# ah.net
KiCad netlist of a schematic drawn in EAGLE
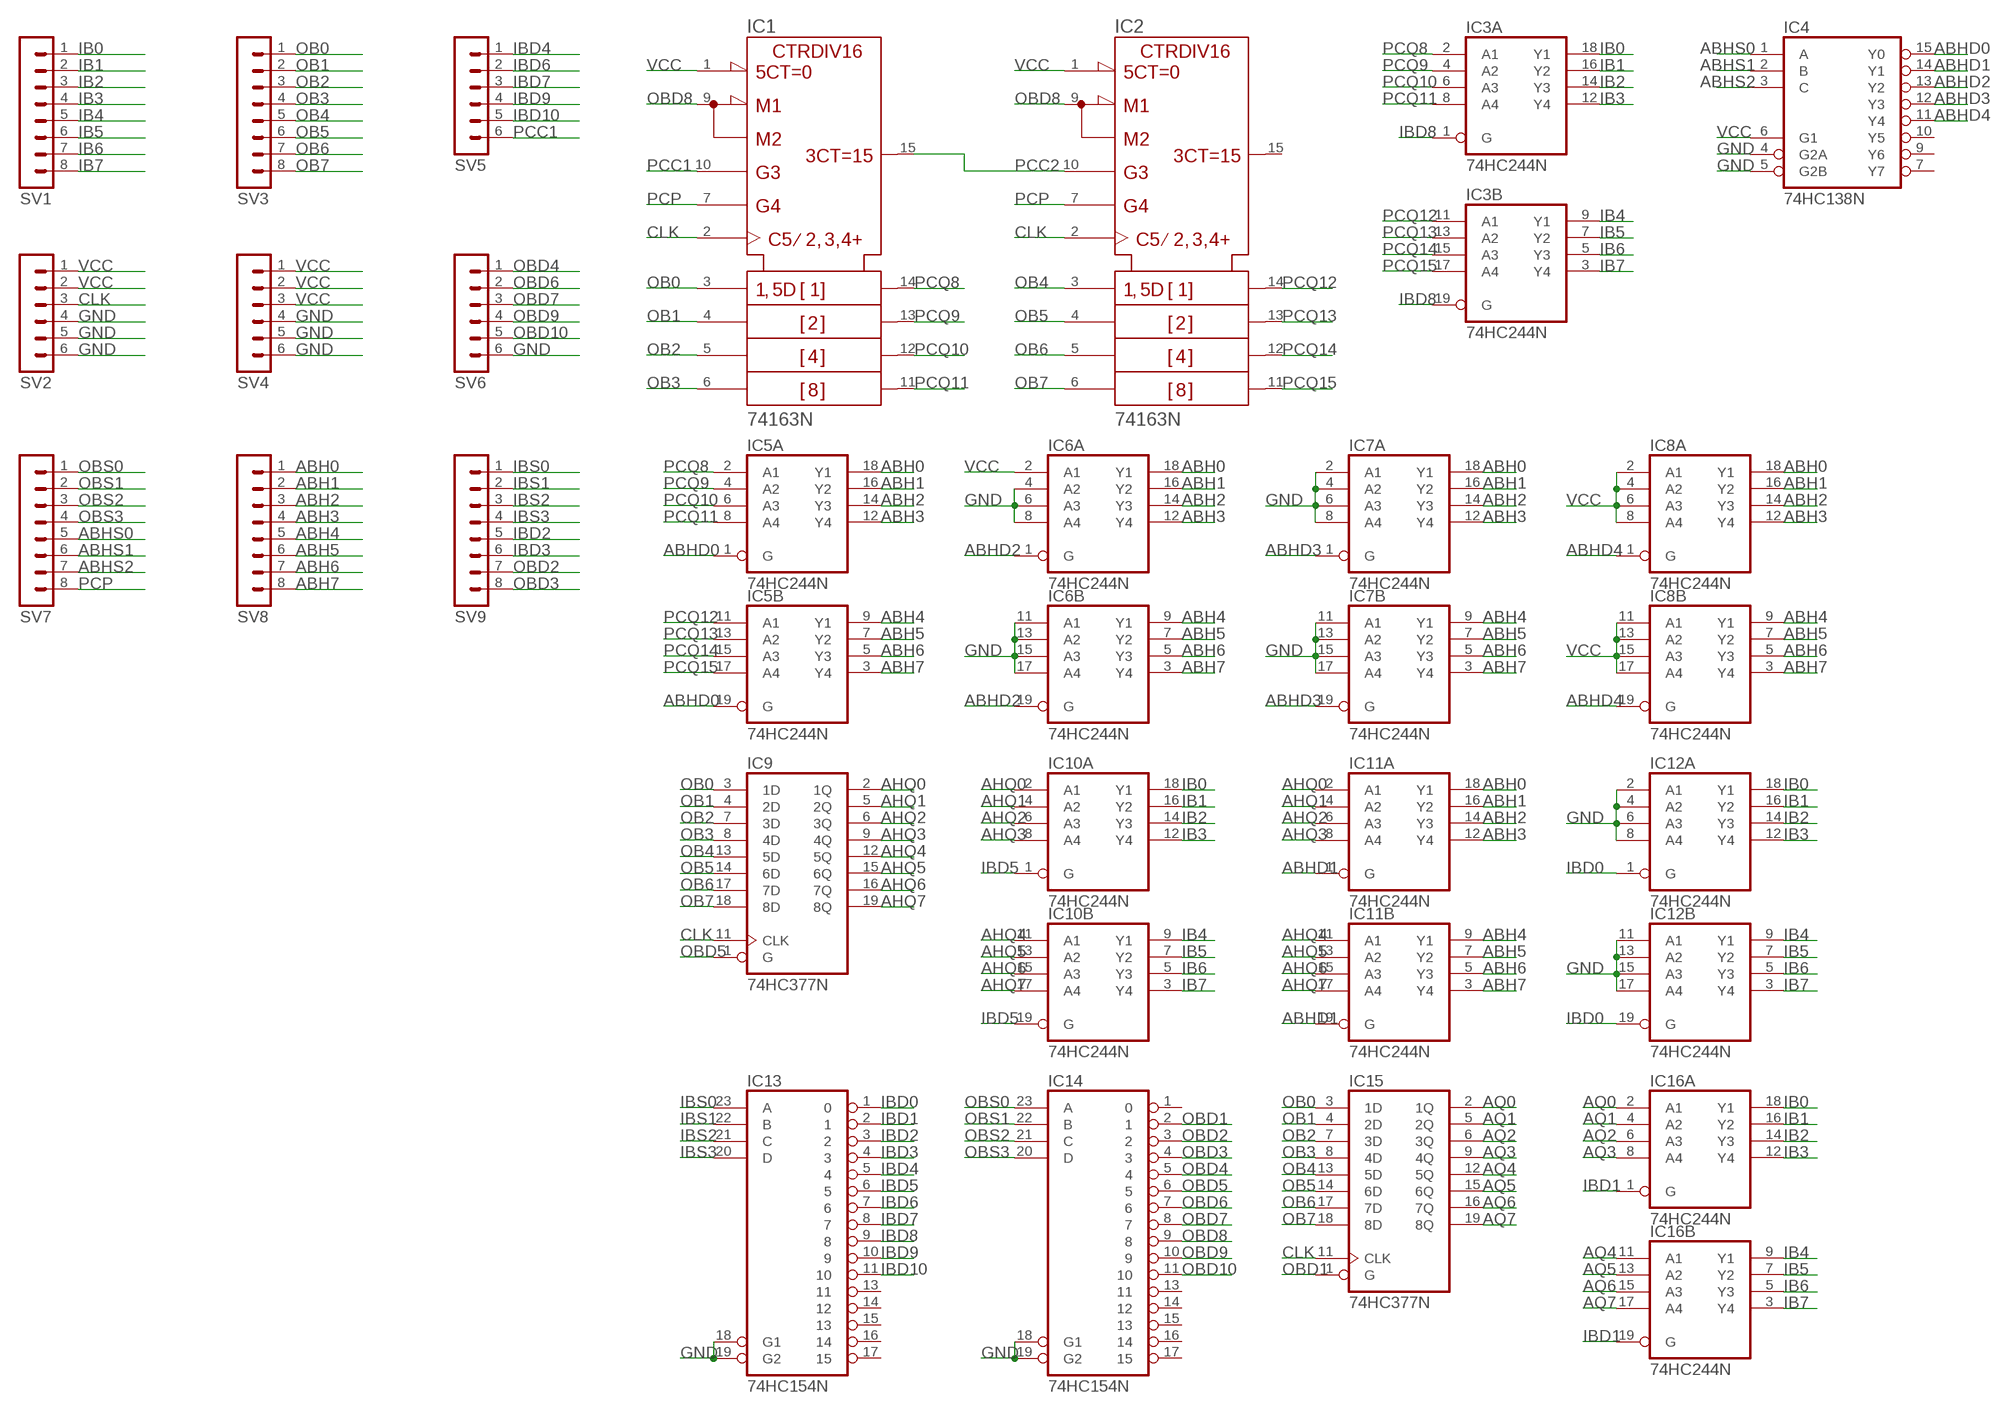
[diagram p0: schematic, sheet 1]

(export (version "E")
  (design (tool "Eeschema 10.0.6"))
  (components
    (comp (ref "IC1")
      (value "74163N")
      (footprint "eagle-import:DIL16")
      (libsource (lib "eagle-import") (part "74163N"))
    )
    (comp (ref "IC2")
      (value "74163N")
      (footprint "eagle-import:DIL16")
      (libsource (lib "eagle-import") (part "74163N"))
    )
    (comp (ref "IC3")
      (value "74HC244N")
      (footprint "eagle-import:DIL20")
      (libsource (lib "eagle-import") (part "74244NHC"))
    )
    (comp (ref "IC4")
      (value "74HC138N")
      (footprint "eagle-import:DIL16")
      (libsource (lib "eagle-import") (part "74138NHC"))
    )
    (comp (ref "IC5")
      (value "74HC244N")
      (footprint "eagle-import:DIL20")
      (libsource (lib "eagle-import") (part "74244NHC"))
    )
    (comp (ref "IC6")
      (value "74HC244N")
      (footprint "eagle-import:DIL20")
      (libsource (lib "eagle-import") (part "74244NHC"))
    )
    (comp (ref "IC7")
      (value "74HC244N")
      (footprint "eagle-import:DIL20")
      (libsource (lib "eagle-import") (part "74244NHC"))
    )
    (comp (ref "IC8")
      (value "74HC244N")
      (footprint "eagle-import:DIL20")
      (libsource (lib "eagle-import") (part "74244NHC"))
    )
    (comp (ref "IC9")
      (value "74HC377N")
      (footprint "eagle-import:DIL20")
      (libsource (lib "eagle-import") (part "74377NHC"))
    )
    (comp (ref "IC10")
      (value "74HC244N")
      (footprint "eagle-import:DIL20")
      (libsource (lib "eagle-import") (part "74244NHC"))
    )
    (comp (ref "IC11")
      (value "74HC244N")
      (footprint "eagle-import:DIL20")
      (libsource (lib "eagle-import") (part "74244NHC"))
    )
    (comp (ref "IC12")
      (value "74HC244N")
      (footprint "eagle-import:DIL20")
      (libsource (lib "eagle-import") (part "74244NHC"))
    )
    (comp (ref "IC13")
      (value "74HC154N")
      (footprint "eagle-import:DIL24-6")
      (libsource (lib "eagle-import") (part "74154NHC"))
    )
    (comp (ref "IC14")
      (value "74HC154N")
      (footprint "eagle-import:DIL24-6")
      (libsource (lib "eagle-import") (part "74154NHC"))
    )
    (comp (ref "IC15")
      (value "74HC377N")
      (footprint "eagle-import:DIL20")
      (libsource (lib "eagle-import") (part "74377NHC"))
    )
    (comp (ref "IC16")
      (value "74HC244N")
      (footprint "eagle-import:DIL20")
      (libsource (lib "eagle-import") (part "74244NHC"))
    )
    (comp (ref "SV1")
      (value "MA08-1")
      (footprint "eagle-import:MA08-1")
      (libsource (lib "eagle-import") (part "MA08-1"))
    )
    (comp (ref "SV2")
      (value "MA06-1")
      (footprint "eagle-import:MA06-1")
      (libsource (lib "eagle-import") (part "MA06-1"))
    )
    (comp (ref "SV3")
      (value "MA08-1")
      (footprint "eagle-import:MA08-1")
      (libsource (lib "eagle-import") (part "MA08-1"))
    )
    (comp (ref "SV4")
      (value "MA06-1")
      (footprint "eagle-import:MA06-1")
      (libsource (lib "eagle-import") (part "MA06-1"))
    )
    (comp (ref "SV5")
      (value "MA06-1")
      (footprint "eagle-import:MA06-1")
      (libsource (lib "eagle-import") (part "MA06-1"))
    )
    (comp (ref "SV6")
      (value "MA06-1")
      (footprint "eagle-import:MA06-1")
      (libsource (lib "eagle-import") (part "MA06-1"))
    )
    (comp (ref "SV7")
      (value "MA08-1")
      (footprint "eagle-import:MA08-1")
      (libsource (lib "eagle-import") (part "MA08-1"))
    )
    (comp (ref "SV8")
      (value "MA08-1")
      (footprint "eagle-import:MA08-1")
      (libsource (lib "eagle-import") (part "MA08-1"))
    )
    (comp (ref "SV9")
      (value "MA08-1")
      (footprint "eagle-import:MA08-1")
      (libsource (lib "eagle-import") (part "MA08-1"))
    )
  )
  (nets
    (net (code "1") (name "/ABH0") (class "Default")
      (node (ref "IC11") (pin "18") (pinfunction "Y1_18") (pintype "tri_state"))
      (node (ref "IC5") (pin "18") (pinfunction "Y1_18") (pintype "tri_state"))
      (node (ref "IC6") (pin "18") (pinfunction "Y1_18") (pintype "tri_state"))
      (node (ref "IC7") (pin "18") (pinfunction "Y1_18") (pintype "tri_state"))
      (node (ref "IC8") (pin "18") (pinfunction "Y1_18") (pintype "tri_state"))
      (node (ref "SV8") (pin "1") (pinfunction "1_1") (pintype "passive"))
    )
    (net (code "2") (name "/ABH1") (class "Default")
      (node (ref "IC11") (pin "16") (pinfunction "Y2_16") (pintype "tri_state"))
      (node (ref "IC5") (pin "16") (pinfunction "Y2_16") (pintype "tri_state"))
      (node (ref "IC6") (pin "16") (pinfunction "Y2_16") (pintype "tri_state"))
      (node (ref "IC7") (pin "16") (pinfunction "Y2_16") (pintype "tri_state"))
      (node (ref "IC8") (pin "16") (pinfunction "Y2_16") (pintype "tri_state"))
      (node (ref "SV8") (pin "2") (pinfunction "2_2") (pintype "passive"))
    )
    (net (code "3") (name "/ABH2") (class "Default")
      (node (ref "IC11") (pin "14") (pinfunction "Y3_14") (pintype "tri_state"))
      (node (ref "IC5") (pin "14") (pinfunction "Y3_14") (pintype "tri_state"))
      (node (ref "IC6") (pin "14") (pinfunction "Y3_14") (pintype "tri_state"))
      (node (ref "IC7") (pin "14") (pinfunction "Y3_14") (pintype "tri_state"))
      (node (ref "IC8") (pin "14") (pinfunction "Y3_14") (pintype "tri_state"))
      (node (ref "SV8") (pin "3") (pinfunction "3_3") (pintype "passive"))
    )
    (net (code "4") (name "/ABH3") (class "Default")
      (node (ref "IC11") (pin "12") (pinfunction "Y4_12") (pintype "tri_state"))
      (node (ref "IC5") (pin "12") (pinfunction "Y4_12") (pintype "tri_state"))
      (node (ref "IC6") (pin "12") (pinfunction "Y4_12") (pintype "tri_state"))
      (node (ref "IC7") (pin "12") (pinfunction "Y4_12") (pintype "tri_state"))
      (node (ref "IC8") (pin "12") (pinfunction "Y4_12") (pintype "tri_state"))
      (node (ref "SV8") (pin "4") (pinfunction "4_4") (pintype "passive"))
    )
    (net (code "5") (name "/ABH4") (class "Default")
      (node (ref "IC11") (pin "9") (pinfunction "Y1_9") (pintype "tri_state"))
      (node (ref "IC5") (pin "9") (pinfunction "Y1_9") (pintype "tri_state"))
      (node (ref "IC6") (pin "9") (pinfunction "Y1_9") (pintype "tri_state"))
      (node (ref "IC7") (pin "9") (pinfunction "Y1_9") (pintype "tri_state"))
      (node (ref "IC8") (pin "9") (pinfunction "Y1_9") (pintype "tri_state"))
      (node (ref "SV8") (pin "5") (pinfunction "5_5") (pintype "passive"))
    )
    (net (code "6") (name "/ABH5") (class "Default")
      (node (ref "IC11") (pin "7") (pinfunction "Y2_7") (pintype "tri_state"))
      (node (ref "IC5") (pin "7") (pinfunction "Y2_7") (pintype "tri_state"))
      (node (ref "IC6") (pin "7") (pinfunction "Y2_7") (pintype "tri_state"))
      (node (ref "IC7") (pin "7") (pinfunction "Y2_7") (pintype "tri_state"))
      (node (ref "IC8") (pin "7") (pinfunction "Y2_7") (pintype "tri_state"))
      (node (ref "SV8") (pin "6") (pinfunction "6_6") (pintype "passive"))
    )
    (net (code "7") (name "/ABH6") (class "Default")
      (node (ref "IC11") (pin "5") (pinfunction "Y3_5") (pintype "tri_state"))
      (node (ref "IC5") (pin "5") (pinfunction "Y3_5") (pintype "tri_state"))
      (node (ref "IC6") (pin "5") (pinfunction "Y3_5") (pintype "tri_state"))
      (node (ref "IC7") (pin "5") (pinfunction "Y3_5") (pintype "tri_state"))
      (node (ref "IC8") (pin "5") (pinfunction "Y3_5") (pintype "tri_state"))
      (node (ref "SV8") (pin "7") (pinfunction "7_7") (pintype "passive"))
    )
    (net (code "8") (name "/ABH7") (class "Default")
      (node (ref "IC11") (pin "3") (pinfunction "Y4_3") (pintype "tri_state"))
      (node (ref "IC5") (pin "3") (pinfunction "Y4_3") (pintype "tri_state"))
      (node (ref "IC6") (pin "3") (pinfunction "Y4_3") (pintype "tri_state"))
      (node (ref "IC7") (pin "3") (pinfunction "Y4_3") (pintype "tri_state"))
      (node (ref "IC8") (pin "3") (pinfunction "Y4_3") (pintype "tri_state"))
      (node (ref "SV8") (pin "8") (pinfunction "8_8") (pintype "passive"))
    )
    (net (code "9") (name "/ABHD0") (class "Default")
      (node (ref "IC4") (pin "15") (pinfunction "Y0_15") (pintype "output"))
      (node (ref "IC5") (pin "1") (pinfunction "G_1") (pintype "input"))
      (node (ref "IC5") (pin "19") (pinfunction "G_19") (pintype "input"))
    )
    (net (code "10") (name "/ABHD1") (class "Default")
      (node (ref "IC11") (pin "1") (pinfunction "G_1") (pintype "input"))
      (node (ref "IC11") (pin "19") (pinfunction "G_19") (pintype "input"))
      (node (ref "IC4") (pin "14") (pinfunction "Y1_14") (pintype "output"))
    )
    (net (code "11") (name "/ABHD2") (class "Default")
      (node (ref "IC4") (pin "13") (pinfunction "Y2_13") (pintype "output"))
      (node (ref "IC6") (pin "1") (pinfunction "G_1") (pintype "input"))
      (node (ref "IC6") (pin "19") (pinfunction "G_19") (pintype "input"))
    )
    (net (code "12") (name "/ABHD3") (class "Default")
      (node (ref "IC4") (pin "12") (pinfunction "Y3_12") (pintype "output"))
      (node (ref "IC7") (pin "1") (pinfunction "G_1") (pintype "input"))
      (node (ref "IC7") (pin "19") (pinfunction "G_19") (pintype "input"))
    )
    (net (code "13") (name "/ABHD4") (class "Default")
      (node (ref "IC4") (pin "11") (pinfunction "Y4_11") (pintype "output"))
      (node (ref "IC8") (pin "1") (pinfunction "G_1") (pintype "input"))
      (node (ref "IC8") (pin "19") (pinfunction "G_19") (pintype "input"))
    )
    (net (code "14") (name "/ABHS0") (class "Default")
      (node (ref "IC4") (pin "1") (pinfunction "A_1") (pintype "input"))
      (node (ref "SV7") (pin "5") (pinfunction "5_5") (pintype "passive"))
    )
    (net (code "15") (name "/ABHS1") (class "Default")
      (node (ref "IC4") (pin "2") (pinfunction "B_2") (pintype "input"))
      (node (ref "SV7") (pin "6") (pinfunction "6_6") (pintype "passive"))
    )
    (net (code "16") (name "/ABHS2") (class "Default")
      (node (ref "IC4") (pin "3") (pinfunction "C_3") (pintype "input"))
      (node (ref "SV7") (pin "7") (pinfunction "7_7") (pintype "passive"))
    )
    (net (code "17") (name "/AHQ0") (class "Default")
      (node (ref "IC10") (pin "2") (pinfunction "A1_2") (pintype "input"))
      (node (ref "IC11") (pin "2") (pinfunction "A1_2") (pintype "input"))
      (node (ref "IC9") (pin "2") (pinfunction "1Q_2") (pintype "output"))
    )
    (net (code "18") (name "/AHQ1") (class "Default")
      (node (ref "IC10") (pin "4") (pinfunction "A2_4") (pintype "input"))
      (node (ref "IC11") (pin "4") (pinfunction "A2_4") (pintype "input"))
      (node (ref "IC9") (pin "5") (pinfunction "2Q_5") (pintype "output"))
    )
    (net (code "19") (name "/AHQ2") (class "Default")
      (node (ref "IC10") (pin "6") (pinfunction "A3_6") (pintype "input"))
      (node (ref "IC11") (pin "6") (pinfunction "A3_6") (pintype "input"))
      (node (ref "IC9") (pin "6") (pinfunction "3Q_6") (pintype "output"))
    )
    (net (code "20") (name "/AHQ3") (class "Default")
      (node (ref "IC10") (pin "8") (pinfunction "A4_8") (pintype "input"))
      (node (ref "IC11") (pin "8") (pinfunction "A4_8") (pintype "input"))
      (node (ref "IC9") (pin "9") (pinfunction "4Q_9") (pintype "output"))
    )
    (net (code "21") (name "/AHQ4") (class "Default")
      (node (ref "IC10") (pin "11") (pinfunction "A1_11") (pintype "input"))
      (node (ref "IC11") (pin "11") (pinfunction "A1_11") (pintype "input"))
      (node (ref "IC9") (pin "12") (pinfunction "5Q_12") (pintype "output"))
    )
    (net (code "22") (name "/AHQ5") (class "Default")
      (node (ref "IC10") (pin "13") (pinfunction "A2_13") (pintype "input"))
      (node (ref "IC11") (pin "13") (pinfunction "A2_13") (pintype "input"))
      (node (ref "IC9") (pin "15") (pinfunction "6Q_15") (pintype "output"))
    )
    (net (code "23") (name "/AHQ6") (class "Default")
      (node (ref "IC10") (pin "15") (pinfunction "A3_15") (pintype "input"))
      (node (ref "IC11") (pin "15") (pinfunction "A3_15") (pintype "input"))
      (node (ref "IC9") (pin "16") (pinfunction "7Q_16") (pintype "output"))
    )
    (net (code "24") (name "/AHQ7") (class "Default")
      (node (ref "IC10") (pin "17") (pinfunction "A4_17") (pintype "input"))
      (node (ref "IC11") (pin "17") (pinfunction "A4_17") (pintype "input"))
      (node (ref "IC9") (pin "19") (pinfunction "8Q_19") (pintype "output"))
    )
    (net (code "25") (name "/AQ0") (class "Default")
      (node (ref "IC15") (pin "2") (pinfunction "1Q_2") (pintype "output"))
      (node (ref "IC16") (pin "2") (pinfunction "A1_2") (pintype "input"))
    )
    (net (code "26") (name "/AQ1") (class "Default")
      (node (ref "IC15") (pin "5") (pinfunction "2Q_5") (pintype "output"))
      (node (ref "IC16") (pin "4") (pinfunction "A2_4") (pintype "input"))
    )
    (net (code "27") (name "/AQ2") (class "Default")
      (node (ref "IC15") (pin "6") (pinfunction "3Q_6") (pintype "output"))
      (node (ref "IC16") (pin "6") (pinfunction "A3_6") (pintype "input"))
    )
    (net (code "28") (name "/AQ3") (class "Default")
      (node (ref "IC15") (pin "9") (pinfunction "4Q_9") (pintype "output"))
      (node (ref "IC16") (pin "8") (pinfunction "A4_8") (pintype "input"))
    )
    (net (code "29") (name "/AQ4") (class "Default")
      (node (ref "IC15") (pin "12") (pinfunction "5Q_12") (pintype "output"))
      (node (ref "IC16") (pin "11") (pinfunction "A1_11") (pintype "input"))
    )
    (net (code "30") (name "/AQ5") (class "Default")
      (node (ref "IC15") (pin "15") (pinfunction "6Q_15") (pintype "output"))
      (node (ref "IC16") (pin "13") (pinfunction "A2_13") (pintype "input"))
    )
    (net (code "31") (name "/AQ6") (class "Default")
      (node (ref "IC15") (pin "16") (pinfunction "7Q_16") (pintype "output"))
      (node (ref "IC16") (pin "15") (pinfunction "A3_15") (pintype "input"))
    )
    (net (code "32") (name "/AQ7") (class "Default")
      (node (ref "IC15") (pin "19") (pinfunction "8Q_19") (pintype "output"))
      (node (ref "IC16") (pin "17") (pinfunction "A4_17") (pintype "input"))
    )
    (net (code "33") (name "/CLK") (class "Default")
      (node (ref "IC1") (pin "2") (pinfunction "CLK_2") (pintype "input"))
      (node (ref "IC15") (pin "11") (pinfunction "CLK_11") (pintype "input"))
      (node (ref "IC2") (pin "2") (pinfunction "CLK_2") (pintype "input"))
      (node (ref "IC9") (pin "11") (pinfunction "CLK_11") (pintype "input"))
      (node (ref "SV2") (pin "3") (pinfunction "3_3") (pintype "passive"))
    )
    (net (code "34") (name "/GND") (class "Default")
      (node (ref "IC12") (pin "11") (pinfunction "A1_11") (pintype "input"))
      (node (ref "IC12") (pin "13") (pinfunction "A2_13") (pintype "input"))
      (node (ref "IC12") (pin "15") (pinfunction "A3_15") (pintype "input"))
      (node (ref "IC12") (pin "17") (pinfunction "A4_17") (pintype "input"))
      (node (ref "IC12") (pin "2") (pinfunction "A1_2") (pintype "input"))
      (node (ref "IC12") (pin "4") (pinfunction "A2_4") (pintype "input"))
      (node (ref "IC12") (pin "6") (pinfunction "A3_6") (pintype "input"))
      (node (ref "IC12") (pin "8") (pinfunction "A4_8") (pintype "input"))
      (node (ref "IC13") (pin "18") (pinfunction "G1_18") (pintype "input"))
      (node (ref "IC13") (pin "19") (pinfunction "G2_19") (pintype "input"))
      (node (ref "IC14") (pin "18") (pinfunction "G1_18") (pintype "input"))
      (node (ref "IC14") (pin "19") (pinfunction "G2_19") (pintype "input"))
      (node (ref "IC4") (pin "4") (pinfunction "G2A_4") (pintype "input"))
      (node (ref "IC4") (pin "5") (pinfunction "G2B_5") (pintype "input"))
      (node (ref "IC6") (pin "11") (pinfunction "A1_11") (pintype "input"))
      (node (ref "IC6") (pin "13") (pinfunction "A2_13") (pintype "input"))
      (node (ref "IC6") (pin "15") (pinfunction "A3_15") (pintype "input"))
      (node (ref "IC6") (pin "17") (pinfunction "A4_17") (pintype "input"))
      (node (ref "IC6") (pin "4") (pinfunction "A2_4") (pintype "input"))
      (node (ref "IC6") (pin "6") (pinfunction "A3_6") (pintype "input"))
      (node (ref "IC6") (pin "8") (pinfunction "A4_8") (pintype "input"))
      (node (ref "IC7") (pin "11") (pinfunction "A1_11") (pintype "input"))
      (node (ref "IC7") (pin "13") (pinfunction "A2_13") (pintype "input"))
      (node (ref "IC7") (pin "15") (pinfunction "A3_15") (pintype "input"))
      (node (ref "IC7") (pin "17") (pinfunction "A4_17") (pintype "input"))
      (node (ref "IC7") (pin "2") (pinfunction "A1_2") (pintype "input"))
      (node (ref "IC7") (pin "4") (pinfunction "A2_4") (pintype "input"))
      (node (ref "IC7") (pin "6") (pinfunction "A3_6") (pintype "input"))
      (node (ref "IC7") (pin "8") (pinfunction "A4_8") (pintype "input"))
      (node (ref "SV2") (pin "4") (pinfunction "4_4") (pintype "passive"))
      (node (ref "SV2") (pin "5") (pinfunction "5_5") (pintype "passive"))
      (node (ref "SV2") (pin "6") (pinfunction "6_6") (pintype "passive"))
      (node (ref "SV4") (pin "4") (pinfunction "4_4") (pintype "passive"))
      (node (ref "SV4") (pin "5") (pinfunction "5_5") (pintype "passive"))
      (node (ref "SV4") (pin "6") (pinfunction "6_6") (pintype "passive"))
      (node (ref "SV6") (pin "6") (pinfunction "6_6") (pintype "passive"))
    )
    (net (code "35") (name "/IB0") (class "Default")
      (node (ref "IC10") (pin "18") (pinfunction "Y1_18") (pintype "tri_state"))
      (node (ref "IC12") (pin "18") (pinfunction "Y1_18") (pintype "tri_state"))
      (node (ref "IC16") (pin "18") (pinfunction "Y1_18") (pintype "tri_state"))
      (node (ref "IC3") (pin "18") (pinfunction "Y1_18") (pintype "tri_state"))
      (node (ref "SV1") (pin "1") (pinfunction "1_1") (pintype "passive"))
    )
    (net (code "36") (name "/IB1") (class "Default")
      (node (ref "IC10") (pin "16") (pinfunction "Y2_16") (pintype "tri_state"))
      (node (ref "IC12") (pin "16") (pinfunction "Y2_16") (pintype "tri_state"))
      (node (ref "IC16") (pin "16") (pinfunction "Y2_16") (pintype "tri_state"))
      (node (ref "IC3") (pin "16") (pinfunction "Y2_16") (pintype "tri_state"))
      (node (ref "SV1") (pin "2") (pinfunction "2_2") (pintype "passive"))
    )
    (net (code "37") (name "/IB2") (class "Default")
      (node (ref "IC10") (pin "14") (pinfunction "Y3_14") (pintype "tri_state"))
      (node (ref "IC12") (pin "14") (pinfunction "Y3_14") (pintype "tri_state"))
      (node (ref "IC16") (pin "14") (pinfunction "Y3_14") (pintype "tri_state"))
      (node (ref "IC3") (pin "14") (pinfunction "Y3_14") (pintype "tri_state"))
      (node (ref "SV1") (pin "3") (pinfunction "3_3") (pintype "passive"))
    )
    (net (code "38") (name "/IB3") (class "Default")
      (node (ref "IC10") (pin "12") (pinfunction "Y4_12") (pintype "tri_state"))
      (node (ref "IC12") (pin "12") (pinfunction "Y4_12") (pintype "tri_state"))
      (node (ref "IC16") (pin "12") (pinfunction "Y4_12") (pintype "tri_state"))
      (node (ref "IC3") (pin "12") (pinfunction "Y4_12") (pintype "tri_state"))
      (node (ref "SV1") (pin "4") (pinfunction "4_4") (pintype "passive"))
    )
    (net (code "39") (name "/IB4") (class "Default")
      (node (ref "IC10") (pin "9") (pinfunction "Y1_9") (pintype "tri_state"))
      (node (ref "IC12") (pin "9") (pinfunction "Y1_9") (pintype "tri_state"))
      (node (ref "IC16") (pin "9") (pinfunction "Y1_9") (pintype "tri_state"))
      (node (ref "IC3") (pin "9") (pinfunction "Y1_9") (pintype "tri_state"))
      (node (ref "SV1") (pin "5") (pinfunction "5_5") (pintype "passive"))
    )
    (net (code "40") (name "/IB5") (class "Default")
      (node (ref "IC10") (pin "7") (pinfunction "Y2_7") (pintype "tri_state"))
      (node (ref "IC12") (pin "7") (pinfunction "Y2_7") (pintype "tri_state"))
      (node (ref "IC16") (pin "7") (pinfunction "Y2_7") (pintype "tri_state"))
      (node (ref "IC3") (pin "7") (pinfunction "Y2_7") (pintype "tri_state"))
      (node (ref "SV1") (pin "6") (pinfunction "6_6") (pintype "passive"))
    )
    (net (code "41") (name "/IB6") (class "Default")
      (node (ref "IC10") (pin "5") (pinfunction "Y3_5") (pintype "tri_state"))
      (node (ref "IC12") (pin "5") (pinfunction "Y3_5") (pintype "tri_state"))
      (node (ref "IC16") (pin "5") (pinfunction "Y3_5") (pintype "tri_state"))
      (node (ref "IC3") (pin "5") (pinfunction "Y3_5") (pintype "tri_state"))
      (node (ref "SV1") (pin "7") (pinfunction "7_7") (pintype "passive"))
    )
    (net (code "42") (name "/IB7") (class "Default")
      (node (ref "IC10") (pin "3") (pinfunction "Y4_3") (pintype "tri_state"))
      (node (ref "IC12") (pin "3") (pinfunction "Y4_3") (pintype "tri_state"))
      (node (ref "IC16") (pin "3") (pinfunction "Y4_3") (pintype "tri_state"))
      (node (ref "IC3") (pin "3") (pinfunction "Y4_3") (pintype "tri_state"))
      (node (ref "SV1") (pin "8") (pinfunction "8_8") (pintype "passive"))
    )
    (net (code "43") (name "/IBD0") (class "Default")
      (node (ref "IC12") (pin "1") (pinfunction "G_1") (pintype "input"))
      (node (ref "IC12") (pin "19") (pinfunction "G_19") (pintype "input"))
      (node (ref "IC13") (pin "1") (pinfunction "0_1") (pintype "output"))
    )
    (net (code "44") (name "/IBD1") (class "Default")
      (node (ref "IC13") (pin "2") (pinfunction "1_2") (pintype "output"))
      (node (ref "IC16") (pin "1") (pinfunction "G_1") (pintype "input"))
      (node (ref "IC16") (pin "19") (pinfunction "G_19") (pintype "input"))
    )
    (net (code "45") (name "/IBD2") (class "Default")
      (node (ref "IC13") (pin "3") (pinfunction "2_3") (pintype "output"))
      (node (ref "SV9") (pin "5") (pinfunction "5_5") (pintype "passive"))
    )
    (net (code "46") (name "/IBD3") (class "Default")
      (node (ref "IC13") (pin "4") (pinfunction "3_4") (pintype "output"))
      (node (ref "SV9") (pin "6") (pinfunction "6_6") (pintype "passive"))
    )
    (net (code "47") (name "/IBD4") (class "Default")
      (node (ref "IC13") (pin "5") (pinfunction "4_5") (pintype "output"))
      (node (ref "SV5") (pin "1") (pinfunction "1_1") (pintype "passive"))
    )
    (net (code "48") (name "/IBD5") (class "Default")
      (node (ref "IC10") (pin "1") (pinfunction "G_1") (pintype "input"))
      (node (ref "IC10") (pin "19") (pinfunction "G_19") (pintype "input"))
      (node (ref "IC13") (pin "6") (pinfunction "5_6") (pintype "output"))
    )
    (net (code "49") (name "/IBD6") (class "Default")
      (node (ref "IC13") (pin "7") (pinfunction "6_7") (pintype "output"))
      (node (ref "SV5") (pin "2") (pinfunction "2_2") (pintype "passive"))
    )
    (net (code "50") (name "/IBD7") (class "Default")
      (node (ref "IC13") (pin "8") (pinfunction "7_8") (pintype "output"))
      (node (ref "SV5") (pin "3") (pinfunction "3_3") (pintype "passive"))
    )
    (net (code "51") (name "/IBD8") (class "Default")
      (node (ref "IC13") (pin "9") (pinfunction "8_9") (pintype "output"))
      (node (ref "IC3") (pin "1") (pinfunction "G_1") (pintype "input"))
      (node (ref "IC3") (pin "19") (pinfunction "G_19") (pintype "input"))
    )
    (net (code "52") (name "/IBD9") (class "Default")
      (node (ref "IC13") (pin "10") (pinfunction "9_10") (pintype "output"))
      (node (ref "SV5") (pin "4") (pinfunction "4_4") (pintype "passive"))
    )
    (net (code "53") (name "/IBD10") (class "Default")
      (node (ref "IC13") (pin "11") (pinfunction "10_11") (pintype "output"))
      (node (ref "SV5") (pin "5") (pinfunction "5_5") (pintype "passive"))
    )
    (net (code "54") (name "/IBS0") (class "Default")
      (node (ref "IC13") (pin "23") (pinfunction "A_23") (pintype "input"))
      (node (ref "SV9") (pin "1") (pinfunction "1_1") (pintype "passive"))
    )
    (net (code "55") (name "/IBS1") (class "Default")
      (node (ref "IC13") (pin "22") (pinfunction "B_22") (pintype "input"))
      (node (ref "SV9") (pin "2") (pinfunction "2_2") (pintype "passive"))
    )
    (net (code "56") (name "/IBS2") (class "Default")
      (node (ref "IC13") (pin "21") (pinfunction "C_21") (pintype "input"))
      (node (ref "SV9") (pin "3") (pinfunction "3_3") (pintype "passive"))
    )
    (net (code "57") (name "/IBS3") (class "Default")
      (node (ref "IC13") (pin "20") (pinfunction "D_20") (pintype "input"))
      (node (ref "SV9") (pin "4") (pinfunction "4_4") (pintype "passive"))
    )
    (net (code "58") (name "/OB0") (class "Default")
      (node (ref "IC1") (pin "3") (pinfunction "A_3") (pintype "input"))
      (node (ref "IC15") (pin "3") (pinfunction "1D_3") (pintype "input"))
      (node (ref "IC9") (pin "3") (pinfunction "1D_3") (pintype "input"))
      (node (ref "SV3") (pin "1") (pinfunction "1_1") (pintype "passive"))
    )
    (net (code "59") (name "/OB1") (class "Default")
      (node (ref "IC1") (pin "4") (pinfunction "B_4") (pintype "input"))
      (node (ref "IC15") (pin "4") (pinfunction "2D_4") (pintype "input"))
      (node (ref "IC9") (pin "4") (pinfunction "2D_4") (pintype "input"))
      (node (ref "SV3") (pin "2") (pinfunction "2_2") (pintype "passive"))
    )
    (net (code "60") (name "/OB2") (class "Default")
      (node (ref "IC1") (pin "5") (pinfunction "C_5") (pintype "input"))
      (node (ref "IC15") (pin "7") (pinfunction "3D_7") (pintype "input"))
      (node (ref "IC9") (pin "7") (pinfunction "3D_7") (pintype "input"))
      (node (ref "SV3") (pin "3") (pinfunction "3_3") (pintype "passive"))
    )
    (net (code "61") (name "/OB3") (class "Default")
      (node (ref "IC1") (pin "6") (pinfunction "D_6") (pintype "input"))
      (node (ref "IC15") (pin "8") (pinfunction "4D_8") (pintype "input"))
      (node (ref "IC9") (pin "8") (pinfunction "4D_8") (pintype "input"))
      (node (ref "SV3") (pin "4") (pinfunction "4_4") (pintype "passive"))
    )
    (net (code "62") (name "/OB4") (class "Default")
      (node (ref "IC15") (pin "13") (pinfunction "5D_13") (pintype "input"))
      (node (ref "IC2") (pin "3") (pinfunction "A_3") (pintype "input"))
      (node (ref "IC9") (pin "13") (pinfunction "5D_13") (pintype "input"))
      (node (ref "SV3") (pin "5") (pinfunction "5_5") (pintype "passive"))
    )
    (net (code "63") (name "/OB5") (class "Default")
      (node (ref "IC15") (pin "14") (pinfunction "6D_14") (pintype "input"))
      (node (ref "IC2") (pin "4") (pinfunction "B_4") (pintype "input"))
      (node (ref "IC9") (pin "14") (pinfunction "6D_14") (pintype "input"))
      (node (ref "SV3") (pin "6") (pinfunction "6_6") (pintype "passive"))
    )
    (net (code "64") (name "/OB6") (class "Default")
      (node (ref "IC15") (pin "17") (pinfunction "7D_17") (pintype "input"))
      (node (ref "IC2") (pin "5") (pinfunction "C_5") (pintype "input"))
      (node (ref "IC9") (pin "17") (pinfunction "7D_17") (pintype "input"))
      (node (ref "SV3") (pin "7") (pinfunction "7_7") (pintype "passive"))
    )
    (net (code "65") (name "/OB7") (class "Default")
      (node (ref "IC15") (pin "18") (pinfunction "8D_18") (pintype "input"))
      (node (ref "IC2") (pin "6") (pinfunction "D_6") (pintype "input"))
      (node (ref "IC9") (pin "18") (pinfunction "8D_18") (pintype "input"))
      (node (ref "SV3") (pin "8") (pinfunction "8_8") (pintype "passive"))
    )
    (net (code "66") (name "/OBD1") (class "Default")
      (node (ref "IC14") (pin "2") (pinfunction "1_2") (pintype "output"))
      (node (ref "IC15") (pin "1") (pinfunction "G_1") (pintype "input"))
    )
    (net (code "67") (name "/OBD2") (class "Default")
      (node (ref "IC14") (pin "3") (pinfunction "2_3") (pintype "output"))
      (node (ref "SV9") (pin "7") (pinfunction "7_7") (pintype "passive"))
    )
    (net (code "68") (name "/OBD3") (class "Default")
      (node (ref "IC14") (pin "4") (pinfunction "3_4") (pintype "output"))
      (node (ref "SV9") (pin "8") (pinfunction "8_8") (pintype "passive"))
    )
    (net (code "69") (name "/OBD4") (class "Default")
      (node (ref "IC14") (pin "5") (pinfunction "4_5") (pintype "output"))
      (node (ref "SV6") (pin "1") (pinfunction "1_1") (pintype "passive"))
    )
    (net (code "70") (name "/OBD5") (class "Default")
      (node (ref "IC14") (pin "6") (pinfunction "5_6") (pintype "output"))
      (node (ref "IC9") (pin "1") (pinfunction "G_1") (pintype "input"))
    )
    (net (code "71") (name "/OBD6") (class "Default")
      (node (ref "IC14") (pin "7") (pinfunction "6_7") (pintype "output"))
      (node (ref "SV6") (pin "2") (pinfunction "2_2") (pintype "passive"))
    )
    (net (code "72") (name "/OBD7") (class "Default")
      (node (ref "IC14") (pin "8") (pinfunction "7_8") (pintype "output"))
      (node (ref "SV6") (pin "3") (pinfunction "3_3") (pintype "passive"))
    )
    (net (code "73") (name "/OBD8") (class "Default")
      (node (ref "IC1") (pin "9") (pinfunction "~{LOAD}_9") (pintype "input"))
      (node (ref "IC14") (pin "9") (pinfunction "8_9") (pintype "output"))
      (node (ref "IC2") (pin "9") (pinfunction "~{LOAD}_9") (pintype "input"))
    )
    (net (code "74") (name "/OBD9") (class "Default")
      (node (ref "IC14") (pin "10") (pinfunction "9_10") (pintype "output"))
      (node (ref "SV6") (pin "4") (pinfunction "4_4") (pintype "passive"))
    )
    (net (code "75") (name "/OBD10") (class "Default")
      (node (ref "IC14") (pin "11") (pinfunction "10_11") (pintype "output"))
      (node (ref "SV6") (pin "5") (pinfunction "5_5") (pintype "passive"))
    )
    (net (code "76") (name "/OBS0") (class "Default")
      (node (ref "IC14") (pin "23") (pinfunction "A_23") (pintype "input"))
      (node (ref "SV7") (pin "1") (pinfunction "1_1") (pintype "passive"))
    )
    (net (code "77") (name "/OBS1") (class "Default")
      (node (ref "IC14") (pin "22") (pinfunction "B_22") (pintype "input"))
      (node (ref "SV7") (pin "2") (pinfunction "2_2") (pintype "passive"))
    )
    (net (code "78") (name "/OBS2") (class "Default")
      (node (ref "IC14") (pin "21") (pinfunction "C_21") (pintype "input"))
      (node (ref "SV7") (pin "3") (pinfunction "3_3") (pintype "passive"))
    )
    (net (code "79") (name "/OBS3") (class "Default")
      (node (ref "IC14") (pin "20") (pinfunction "D_20") (pintype "input"))
      (node (ref "SV7") (pin "4") (pinfunction "4_4") (pintype "passive"))
    )
    (net (code "80") (name "/PCC1") (class "Default")
      (node (ref "IC1") (pin "10") (pinfunction "ENT_10") (pintype "input"))
      (node (ref "SV5") (pin "6") (pinfunction "6_6") (pintype "passive"))
    )
    (net (code "81") (name "/PCC2") (class "Default")
      (node (ref "IC1") (pin "15") (pinfunction "RCO_15") (pintype "output"))
      (node (ref "IC2") (pin "10") (pinfunction "ENT_10") (pintype "input"))
    )
    (net (code "82") (name "/PCP") (class "Default")
      (node (ref "IC1") (pin "7") (pinfunction "ENP_7") (pintype "input"))
      (node (ref "IC2") (pin "7") (pinfunction "ENP_7") (pintype "input"))
      (node (ref "SV7") (pin "8") (pinfunction "8_8") (pintype "passive"))
    )
    (net (code "83") (name "/PCQ8") (class "Default")
      (node (ref "IC1") (pin "14") (pinfunction "QA_14") (pintype "output"))
      (node (ref "IC3") (pin "2") (pinfunction "A1_2") (pintype "input"))
      (node (ref "IC5") (pin "2") (pinfunction "A1_2") (pintype "input"))
    )
    (net (code "84") (name "/PCQ9") (class "Default")
      (node (ref "IC1") (pin "13") (pinfunction "QB_13") (pintype "output"))
      (node (ref "IC3") (pin "4") (pinfunction "A2_4") (pintype "input"))
      (node (ref "IC5") (pin "4") (pinfunction "A2_4") (pintype "input"))
    )
    (net (code "85") (name "/PCQ10") (class "Default")
      (node (ref "IC1") (pin "12") (pinfunction "QC_12") (pintype "output"))
      (node (ref "IC3") (pin "6") (pinfunction "A3_6") (pintype "input"))
      (node (ref "IC5") (pin "6") (pinfunction "A3_6") (pintype "input"))
    )
    (net (code "86") (name "/PCQ11") (class "Default")
      (node (ref "IC1") (pin "11") (pinfunction "QD_11") (pintype "output"))
      (node (ref "IC3") (pin "8") (pinfunction "A4_8") (pintype "input"))
      (node (ref "IC5") (pin "8") (pinfunction "A4_8") (pintype "input"))
    )
    (net (code "87") (name "/PCQ12") (class "Default")
      (node (ref "IC2") (pin "14") (pinfunction "QA_14") (pintype "output"))
      (node (ref "IC3") (pin "11") (pinfunction "A1_11") (pintype "input"))
      (node (ref "IC5") (pin "11") (pinfunction "A1_11") (pintype "input"))
    )
    (net (code "88") (name "/PCQ13") (class "Default")
      (node (ref "IC2") (pin "13") (pinfunction "QB_13") (pintype "output"))
      (node (ref "IC3") (pin "13") (pinfunction "A2_13") (pintype "input"))
      (node (ref "IC5") (pin "13") (pinfunction "A2_13") (pintype "input"))
    )
    (net (code "89") (name "/PCQ14") (class "Default")
      (node (ref "IC2") (pin "12") (pinfunction "QC_12") (pintype "output"))
      (node (ref "IC3") (pin "15") (pinfunction "A3_15") (pintype "input"))
      (node (ref "IC5") (pin "15") (pinfunction "A3_15") (pintype "input"))
    )
    (net (code "90") (name "/PCQ15") (class "Default")
      (node (ref "IC2") (pin "11") (pinfunction "QD_11") (pintype "output"))
      (node (ref "IC3") (pin "17") (pinfunction "A4_17") (pintype "input"))
      (node (ref "IC5") (pin "17") (pinfunction "A4_17") (pintype "input"))
    )
    (net (code "91") (name "/VCC") (class "Default")
      (node (ref "IC1") (pin "1") (pinfunction "~{CLR}_1") (pintype "input"))
      (node (ref "IC2") (pin "1") (pinfunction "~{CLR}_1") (pintype "input"))
      (node (ref "IC4") (pin "6") (pinfunction "G1_6") (pintype "input"))
      (node (ref "IC6") (pin "2") (pinfunction "A1_2") (pintype "input"))
      (node (ref "IC8") (pin "11") (pinfunction "A1_11") (pintype "input"))
      (node (ref "IC8") (pin "13") (pinfunction "A2_13") (pintype "input"))
      (node (ref "IC8") (pin "15") (pinfunction "A3_15") (pintype "input"))
      (node (ref "IC8") (pin "17") (pinfunction "A4_17") (pintype "input"))
      (node (ref "IC8") (pin "2") (pinfunction "A1_2") (pintype "input"))
      (node (ref "IC8") (pin "4") (pinfunction "A2_4") (pintype "input"))
      (node (ref "IC8") (pin "6") (pinfunction "A3_6") (pintype "input"))
      (node (ref "IC8") (pin "8") (pinfunction "A4_8") (pintype "input"))
      (node (ref "SV2") (pin "1") (pinfunction "1_1") (pintype "passive"))
      (node (ref "SV2") (pin "2") (pinfunction "2_2") (pintype "passive"))
      (node (ref "SV4") (pin "1") (pinfunction "1_1") (pintype "passive"))
      (node (ref "SV4") (pin "2") (pinfunction "2_2") (pintype "passive"))
      (node (ref "SV4") (pin "3") (pinfunction "3_3") (pintype "passive"))
    )
    (net (code "92") (name "unconnected-(IC2C-RCO-Pad15)") (class "Default")
      (node (ref "IC2") (pin "15") (pinfunction "RCO_15") (pintype "output"))
    )
    (net (code "93") (name "unconnected-(IC4A-Y5-Pad10)") (class "Default")
      (node (ref "IC4") (pin "10") (pinfunction "Y5_10") (pintype "output"))
    )
    (net (code "94") (name "unconnected-(IC4A-Y6-Pad9)") (class "Default")
      (node (ref "IC4") (pin "9") (pinfunction "Y6_9") (pintype "output"))
    )
    (net (code "95") (name "unconnected-(IC4A-Y7-Pad7)") (class "Default")
      (node (ref "IC4") (pin "7") (pinfunction "Y7_7") (pintype "output"))
    )
    (net (code "96") (name "unconnected-(IC13A-11-Pad13)") (class "Default")
      (node (ref "IC13") (pin "13") (pinfunction "11_13") (pintype "output"))
    )
    (net (code "97") (name "unconnected-(IC13A-12-Pad14)") (class "Default")
      (node (ref "IC13") (pin "14") (pinfunction "12_14") (pintype "output"))
    )
    (net (code "98") (name "unconnected-(IC13A-13-Pad15)") (class "Default")
      (node (ref "IC13") (pin "15") (pinfunction "13_15") (pintype "output"))
    )
    (net (code "99") (name "unconnected-(IC13A-14-Pad16)") (class "Default")
      (node (ref "IC13") (pin "16") (pinfunction "14_16") (pintype "output"))
    )
    (net (code "100") (name "unconnected-(IC13A-15-Pad17)") (class "Default")
      (node (ref "IC13") (pin "17") (pinfunction "15_17") (pintype "output"))
    )
    (net (code "101") (name "unconnected-(IC14A-0-Pad1)") (class "Default")
      (node (ref "IC14") (pin "1") (pinfunction "0_1") (pintype "output"))
    )
    (net (code "102") (name "unconnected-(IC14A-11-Pad13)") (class "Default")
      (node (ref "IC14") (pin "13") (pinfunction "11_13") (pintype "output"))
    )
    (net (code "103") (name "unconnected-(IC14A-12-Pad14)") (class "Default")
      (node (ref "IC14") (pin "14") (pinfunction "12_14") (pintype "output"))
    )
    (net (code "104") (name "unconnected-(IC14A-13-Pad15)") (class "Default")
      (node (ref "IC14") (pin "15") (pinfunction "13_15") (pintype "output"))
    )
    (net (code "105") (name "unconnected-(IC14A-14-Pad16)") (class "Default")
      (node (ref "IC14") (pin "16") (pinfunction "14_16") (pintype "output"))
    )
    (net (code "106") (name "unconnected-(IC14A-15-Pad17)") (class "Default")
      (node (ref "IC14") (pin "17") (pinfunction "15_17") (pintype "output"))
    )
  )
)
